# 23-POWER-P12V.net
KiCad netlist of a schematic drawn in Altium Designer
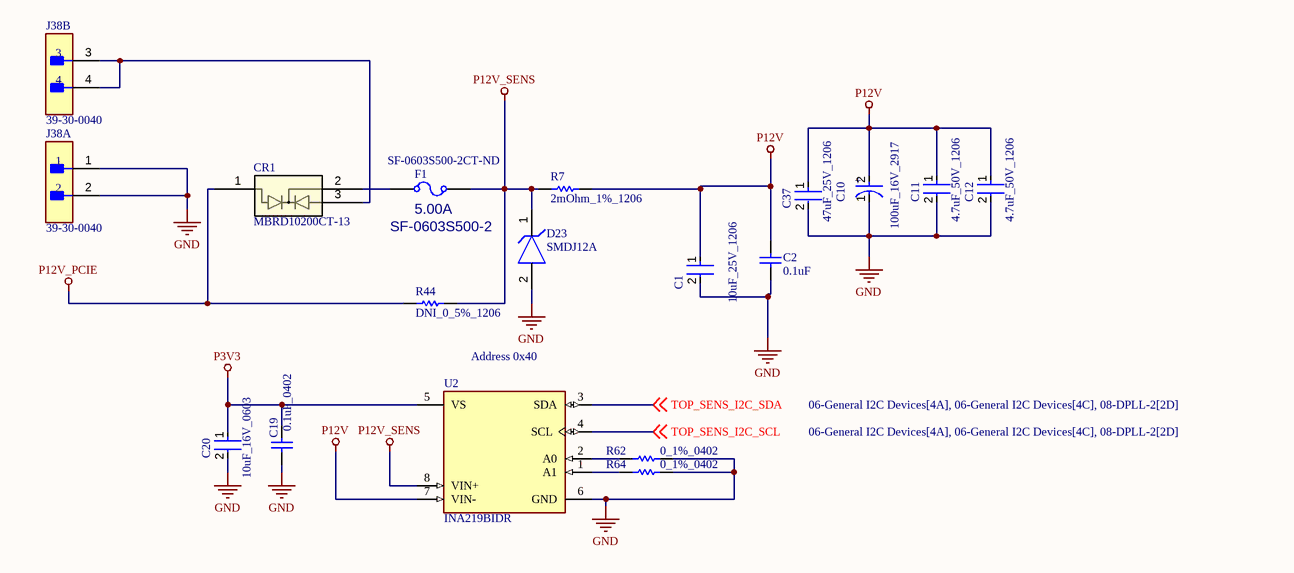
[diagram p0: 23-POWER-P12V.SchDoc]

(export (version "E")
  (design (tool "Eeschema 10.0.6"))
  (components
    (comp (ref "C1")
      (value "10uF_25V_1206")
      (footprint "FP-MK316L-MFG")
      (description "CAP CER 10UF 25V X7R 1206")
      (fields (field (name "TOLERANCE") "10%"))
      (libsource (lib "Altium Content Vault") (part "11868f565c42a9108669ba33697ecf6"))
    )
    (comp (ref "C2")
      (value "0.1uF")
      (footprint "CAPC1608X87X45ML20T05")
      (description "C0603X104K5RACAUTO")
      (fields (field (name "MANUFACTURER") "Kemet"))
      (libsource (lib "Altium Content Vault") (part "CAP"))
    )
    (comp (ref "C10")
      (value "100uF_16V_2917")
      (footprint "FP-T495D107K016ATE125-MFG")
      (description "CAP TANT 100UF 10% 16V 2917")
      (fields (field (name "VOLTAGE") "16V") (field (name "TOLERANCE") "10%"))
      (libsource (lib "Altium Content Vault") (part "a00bbbee19879c290e62620ae7e47b1"))
    )
    (comp (ref "C11")
      (value "4.7uF_50V_1206")
      (footprint "FP-GRM31C-0_2-e0_3_0_8-IPC_C")
      (description "Chip Multilayer Ceramic Capacitors for General Purpose, 1206, 4.7uF, X7R, 15%, 10%, 50V")
      (fields (field (name "VOLTAGE") "50V") (field (name "TOLERANCE") "10%"))
      (libsource (lib "Altium Content Vault") (part "02cd4be3c70576c341d710602a673aa"))
    )
    (comp (ref "C12")
      (value "4.7uF_50V_1206")
      (footprint "FP-GRM31C-0_2-e0_3_0_8-IPC_C")
      (description "Chip Multilayer Ceramic Capacitors for General Purpose, 1206, 4.7uF, X7R, 15%, 10%, 50V")
      (fields (field (name "VOLTAGE") "50V") (field (name "TOLERANCE") "10%"))
      (libsource (lib "Altium Content Vault") (part "02cd4be3c70576c341d710602a673aa"))
    )
    (comp (ref "C19")
      (value "0.1uF_0402")
      (footprint "CAPC1005X56X25NL10T15")
      (fields
        (field (name "PART NUMBER") "LD02YD104KAB2A")
        (field (name "MANUFACTURER") "AVX Interconnect / Elco")
      )
      (libsource (lib "Altium Content Vault") (part "CAP"))
    )
    (comp (ref "C20")
      (value "10uF_16V_0603")
      (footprint "FP-0603-L_1_6_0_2-W_0_8_0-MFG")
      (description "Multilayer Ceramic Capacitor 10uF 16V X5R 20% SMD 0603 T/R")
      (fields (field (name "TOLERANCE") "20%"))
      (libsource (lib "Altium Content Vault") (part "b4654b650e69147ec39a6b967a45e02"))
    )
    (comp (ref "C37")
      (value "47uF_25V_1206")
      (footprint "FP-C3216-160-0_2-MFG")
      (description "Multilayer Ceramic Capacitors 47uF ±20% 25V X5R SMD 1206")
      (fields (field (name "VOLTAGE") "25V") (field (name "TOLERANCE") "20%"))
      (libsource (lib "Altium Content Vault") (part "11868f565c42a9108669ba33697ecf6"))
    )
    (comp (ref "CR1")
      (value "MBRD10200CT-13")
      (footprint "TO252(DPAK)_DIO")
      (description "No Description Available")
      (libsource (lib "MBRD10200CT-13") (part "MBRD10200CT-13"))
    )
    (comp (ref "D23")
      (value "SMDJ12A")
      (footprint "FP-DO-214AB_SMC_J-Bend-MFG")
      (description "TVS DIODE 12V 19.9V DO214AB")
      (libsource (lib "Altium Content Vault") (part "673ecd2ea4d7fb87b4005b0cb348b7d"))
    )
    (comp (ref "F1")
      (value "5.00A")
      (footprint "FUSM1608X60N")
      (description "FUSE SLOW 5.00A 32V M 0603")
      (fields
        (field (name "MFG PART NUM") "SF-0603S500-2")
        (field (name "VALENTIUM PART NUM") "<VALENTIUM>")
        (field (name "SUPPLIER PART NUMBER 1") "SF-0603S500-2CT-ND")
        (field (name "Comment") "FUSE_0603_5.00A")
      )
      (libsource (lib "Passives") (part "FUSE_0603_2.00A"))
    )
    (comp (ref "J38")
      (value "39-30-0040")
      (footprint "FP-39-30-0040-MFG")
      (description "CONN HEADER R/A 4POS 4.2MM")
      (fields
        (field (name "OCTOPART") "https://octopart.com/39-30-0040-molex-277428")
        (field (name "MANUFACTURER") "Molex")
      )
      (libsource (lib "Altium Content Vault") (part "ac72c5313ea981db199dbd0e8237b04"))
    )
    (comp (ref "R7")
      (value "2mOhm_1%_1206")
      (footprint "RESC3216X89X64NL25T25")
      (fields (field (name "MANUFACTURER") "Vishay Dale") (field (name "PART NUMBER") "WSL12062L000FEA18"))
      (libsource (lib "Altium Content Vault") (part "RES"))
    )
    (comp (ref "R44")
      (value "DNI_0_5%_1206")
      (footprint "RESC3116X65X50ML20T20")
      (fields (field (name "PART NUMBER") "CRCW12060000Z0EAHP") (field (name "MANUFACTURER") "Vishay Dale"))
      (libsource (lib "Altium Content Vault") (part "RES"))
    )
    (comp (ref "R62")
      (value "0_1%_0402")
      (footprint "RESC1005X40X25LL05T05")
      (description "Chip Resistor, 0 Ohm, 0.1 W, -55 to 155 degC, 0402 (1005 Metric), RoHS, Tape and Reel")
      (fields (field (name "MANUFACTURER") "Panasonic") (field (name "TOLERANCE") "5%"))
      (libsource (lib "Altium Content Vault") (part "RES-2"))
    )
    (comp (ref "R64")
      (value "0_1%_0402")
      (footprint "RESC1005X40X25LL05T05")
      (description "Chip Resistor, 0 Ohm, 0.1 W, -55 to 155 degC, 0402 (1005 Metric), RoHS, Tape and Reel")
      (fields (field (name "MANUFACTURER") "Panasonic") (field (name "TOLERANCE") "5%"))
      (libsource (lib "Altium Content Vault") (part "RES-2"))
    )
    (comp (ref "U2")
      (value "INA219BIDR")
      (footprint "FP-D0008A-MFG")
      (description "IC MONITOR PWR/CURR BIDIR 8-SOIC")
      (libsource (lib "Altium Content Vault") (part "41cc1aee4cbc9fa2660a15773fa0e79"))
    )
  )
  (nets
    (net (code "1") (name "GND") (class "Default")
      (node (ref "C1") (pin "2") (pinfunction "2_2") (pintype "passive"))
      (node (ref "C10") (pin "1") (pinfunction "C_1") (pintype "passive"))
      (node (ref "C11") (pin "2") (pinfunction "2_2") (pintype "passive"))
      (node (ref "C12") (pin "2") (pinfunction "2_2") (pintype "passive"))
      (node (ref "C19") (pin "1") (pinfunction "1_1") (pintype "passive"))
      (node (ref "C2") (pin "1") (pinfunction "1_1") (pintype "passive"))
      (node (ref "C20") (pin "2") (pinfunction "2_2") (pintype "passive"))
      (node (ref "C37") (pin "2") (pinfunction "2_2") (pintype "passive"))
      (node (ref "D23") (pin "2") (pinfunction "A_2") (pintype "passive"))
      (node (ref "J38") (pin "1") (pinfunction "1_1") (pintype "passive"))
      (node (ref "J38") (pin "2") (pinfunction "2_2") (pintype "passive"))
      (node (ref "R62") (pin "2") (pinfunction "2_2") (pintype "passive"))
      (node (ref "R64") (pin "2") (pinfunction "2_2") (pintype "passive"))
      (node (ref "U2") (pin "6") (pinfunction "GND_6") (pintype "power_in"))
    )
    (net (code "2") (name "Net-(CR1-Pad2)") (class "Default")
      (node (ref "CR1") (pin "2") (pinfunction "2_2") (pintype "passive"))
      (node (ref "F1") (pin "1") (pinfunction "1_1") (pintype "passive"))
    )
    (net (code "3") (name "Net-(CR1-Pad3)") (class "Default")
      (node (ref "CR1") (pin "3") (pinfunction "3_3") (pintype "passive"))
      (node (ref "J38") (pin "3") (pinfunction "3_3") (pintype "passive"))
      (node (ref "J38") (pin "4") (pinfunction "4_4") (pintype "passive"))
    )
    (net (code "4") (name "Net-(U2-A0)") (class "Default")
      (node (ref "R62") (pin "1") (pinfunction "1_1") (pintype "passive"))
      (node (ref "U2") (pin "2") (pinfunction "A0_2") (pintype "input"))
    )
    (net (code "5") (name "Net-(U2-A1)") (class "Default")
      (node (ref "R64") (pin "1") (pinfunction "1_1") (pintype "passive"))
      (node (ref "U2") (pin "1") (pinfunction "A1_1") (pintype "input"))
    )
    (net (code "6") (name "P3V3") (class "Default")
      (node (ref "C19") (pin "2") (pinfunction "2_2") (pintype "passive"))
      (node (ref "C20") (pin "1") (pinfunction "1_1") (pintype "passive"))
      (node (ref "U2") (pin "5") (pinfunction "VS_5") (pintype "power_in"))
    )
    (net (code "7") (name "P12V") (class "Default")
      (node (ref "C1") (pin "1") (pinfunction "1_1") (pintype "passive"))
      (node (ref "C10") (pin "2") (pinfunction "A_2") (pintype "passive"))
      (node (ref "C11") (pin "1") (pinfunction "1_1") (pintype "passive"))
      (node (ref "C12") (pin "1") (pinfunction "1_1") (pintype "passive"))
      (node (ref "C2") (pin "2") (pinfunction "2_2") (pintype "passive"))
      (node (ref "C37") (pin "1") (pinfunction "1_1") (pintype "passive"))
      (node (ref "R7") (pin "2") (pinfunction "2_2") (pintype "passive"))
      (node (ref "U2") (pin "7") (pinfunction "VIN-_7") (pintype "input"))
    )
    (net (code "8") (name "P12V_PCIE") (class "Default")
      (node (ref "CR1") (pin "1") (pinfunction "1_1") (pintype "passive"))
      (node (ref "R44") (pin "1") (pinfunction "1_1") (pintype "passive"))
    )
    (net (code "9") (name "P12V_SENS") (class "Default")
      (node (ref "D23") (pin "1") (pinfunction "C_1") (pintype "passive"))
      (node (ref "F1") (pin "2") (pinfunction "2_2") (pintype "passive"))
      (node (ref "R44") (pin "2") (pinfunction "2_2") (pintype "passive"))
      (node (ref "R7") (pin "1") (pinfunction "1_1") (pintype "passive"))
      (node (ref "U2") (pin "8") (pinfunction "VIN+_8") (pintype "input"))
    )
    (net (code "10") (name "TOP_SENS_I2C_SCL") (class "Default")
      (node (ref "U2") (pin "4") (pinfunction "SCL_4") (pintype "bidirectional"))
    )
    (net (code "11") (name "TOP_SENS_I2C_SDA") (class "Default")
      (node (ref "U2") (pin "3") (pinfunction "SDA_3") (pintype "bidirectional"))
    )
  )
)
